# Temperature_monitoring.net
KiCad netlist of a schematic drawn in Altium Designer
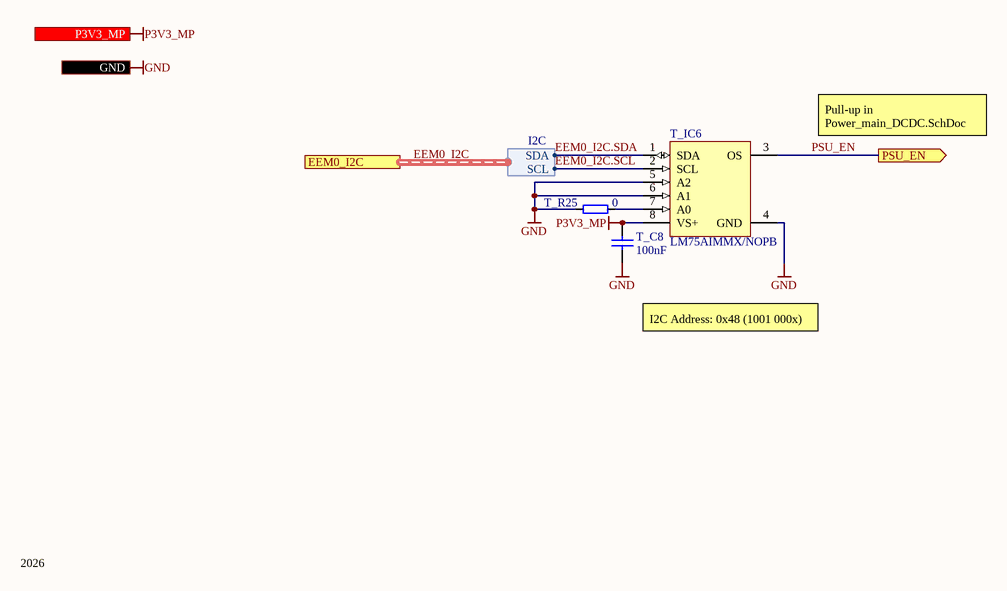
[diagram p0: Temperature_monitoring.SchDoc]

(export (version "E")
  (design (tool "Eeschema 10.0.6"))
  (components
    (comp (ref "T_C8")
      (value "100nF")
      (footprint "CAPC1005X55N")
      (description "Non-polarised capacitor")
      (fields
        (field (name "PART NUMBER") "CC0402_100NF_50V_10%_X7R")
        (field (name "VOLTAGE") "50V")
        (field (name "AUTHOR") "CERN DEM MR")
      )
      (libsource (lib "Capacitors") (part "Capacitor - non polarized"))
    )
    (comp (ref "T_IC6")
      (value "LM75AIMMX/NOPB")
      (footprint "DGK0008A_M")
      (description "Serial Switch/Digital Sensor, 9 Bit(s), 3Cel, Square, 8 Pin, Surface Mount")
      (libsource (lib "TechnoSystem Workspace") (part "SEN-TEMP-LM75-8"))
    )
    (comp (ref "T_R25")
      (value "0")
      (footprint "RESC1005X40N")
      (description "Resistor")
      (fields
        (field (name "PART NUMBER") "R0402_0R_JUMPER")
        (field (name "MANUFACTURER") "GENERIC")
        (field (name "AUTHOR") "CERN DEM JLC")
      )
      (libsource (lib "Resistors") (part "Resistor"))
    )
  )
  (nets
    (net (code "2") (name "/EEM0_I2C.SCL") (class "Default")
      (node (ref "T_IC6") (pin "2") (pinfunction "SCL_2") (pintype "input"))
    )
    (net (code "3") (name "/EEM0_I2C.SDA") (class "Default")
      (node (ref "T_IC6") (pin "1") (pinfunction "SDA_1") (pintype "bidirectional"))
    )
    (net (code "5") (name "/PSU_EN") (class "Default")
      (node (ref "T_IC6") (pin "3") (pinfunction "OS_3") (pintype "open_collector"))
    )
    (net (code "6") (name "GND") (class "Default")
      (node (ref "T_C8") (pin "1") (pinfunction "1_1") (pintype "passive"))
      (node (ref "T_IC6") (pin "4") (pinfunction "GND_4") (pintype "power_in"))
      (node (ref "T_IC6") (pin "5") (pinfunction "A2_5") (pintype "input"))
      (node (ref "T_IC6") (pin "6") (pinfunction "A1_6") (pintype "input"))
      (node (ref "T_R25") (pin "1") (pinfunction "1_1") (pintype "passive"))
    )
    (net (code "7") (name "Net-(T_IC6-A0)") (class "Default")
      (node (ref "T_IC6") (pin "7") (pinfunction "A0_7") (pintype "input"))
      (node (ref "T_R25") (pin "2") (pinfunction "2_2") (pintype "passive"))
    )
    (net (code "8") (name "P3V3_MP") (class "Default")
      (node (ref "T_C8") (pin "2") (pinfunction "2_2") (pintype "passive"))
      (node (ref "T_IC6") (pin "8") (pinfunction "VS+_8") (pintype "power_in"))
    )
  )
)
